# DFPlayer-Wemos-ESPHome.net
KiCad netlist of a schematic drawn in EAGLE
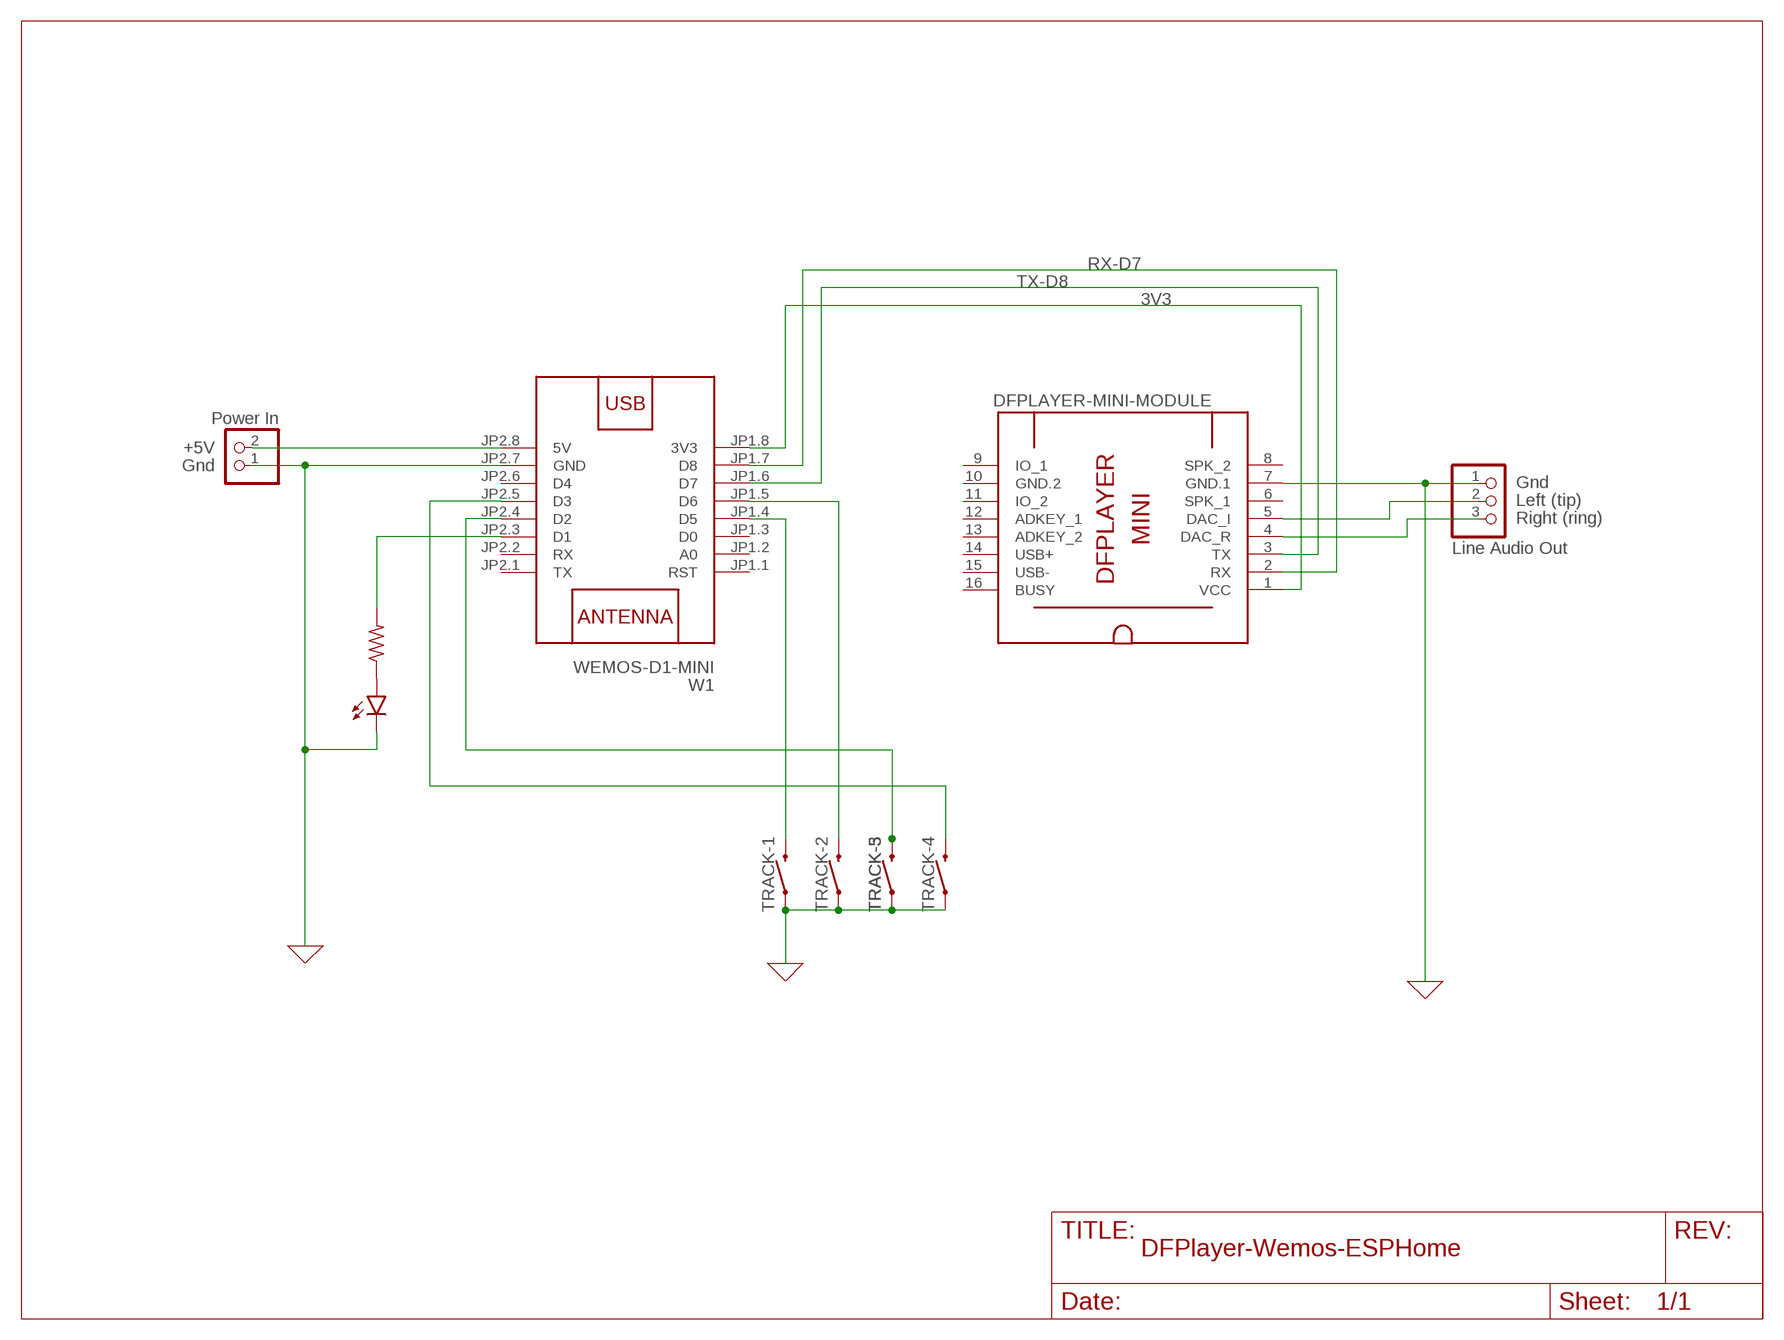
[diagram p0: schematic, sheet 1]

(export (version "E")
  (design (tool "Eeschema 10.0.6"))
  (components
    (comp (ref "D1")
      (value "WP7113SGD")
      (footprint "eagle-import:RADIAL_5MM")
      (fields
        (field (name "DIGIKEY_PART_NUMBER") "754-1735-ND")
        (field (name "MANUFACTURER") "Kingbright")
        (field (name "CREATED_BY") "PCBLayout.com")
      )
      (libsource (lib "eagle-import") (part "WP7113SGD"))
    )
    (comp (ref "JP2")
      (value "Line Audio Out")
      (footprint "eagle-import:1X03")
      (libsource (lib "eagle-import") (part "PINHD-1X3"))
    )
    (comp (ref "JP3")
      (value "Power In")
      (footprint "eagle-import:1X02")
      (libsource (lib "eagle-import") (part "PINHD-1X2"))
    )
    (comp (ref "R1")
      (value "R-US_0204/5")
      (footprint "eagle-import:0204_5")
      (libsource (lib "eagle-import") (part "R-US_0204/5"))
    )
    (comp (ref "TRACK-1")
      (value "MOMENTARY-SWITCH-SPST-PTH-6.0MM")
      (footprint "eagle-import:TACTILE_SWITCH_PTH_6.0MM")
      (libsource (lib "eagle-import") (part "MOMENTARY-SWITCH-SPST-PTH-6.0MM"))
    )
    (comp (ref "TRACK-2")
      (value "MOMENTARY-SWITCH-SPST-PTH-6.0MM")
      (footprint "eagle-import:TACTILE_SWITCH_PTH_6.0MM")
      (libsource (lib "eagle-import") (part "MOMENTARY-SWITCH-SPST-PTH-6.0MM"))
    )
    (comp (ref "TRACK-3")
      (value "MOMENTARY-SWITCH-SPST-PTH-6.0MM")
      (footprint "eagle-import:TACTILE_SWITCH_PTH_6.0MM")
      (libsource (lib "eagle-import") (part "MOMENTARY-SWITCH-SPST-PTH-6.0MM"))
    )
    (comp (ref "TRACK-4")
      (value "MOMENTARY-SWITCH-SPST-PTH-6.0MM")
      (footprint "eagle-import:TACTILE_SWITCH_PTH_6.0MM")
      (libsource (lib "eagle-import") (part "MOMENTARY-SWITCH-SPST-PTH-6.0MM"))
    )
    (comp (ref "TRACK-5")
      (value "MOMENTARY-SWITCH-SPST-PTH-6.0MM")
      (footprint "eagle-import:TACTILE_SWITCH_PTH_6.0MM")
      (libsource (lib "eagle-import") (part "MOMENTARY-SWITCH-SPST-PTH-6.0MM"))
    )
    (comp (ref "U$1")
      (value "DFPLAYER-MINI-MODULE")
      (footprint "eagle-import:DFPLAYER-MINI-MODULE")
      (libsource (lib "eagle-import") (part "DFPLAYER-MINI-MODULE"))
    )
    (comp (ref "W1")
      (value "WEMOS-D1-MINI")
      (footprint "eagle-import:WEMOS-D1-MINI")
      (libsource (lib "eagle-import") (part "WEMOS-D1-MINI"))
    )
  )
  (nets
    (net (code "1") (name "/3V3") (class "Default")
      (node (ref "U$1") (pin "1") (pinfunction "VCC_1") (pintype "power_in"))
      (node (ref "W1") (pin "JP1.8") (pinfunction "3V3_JP1.8") (pintype "power_in"))
    )
    (net (code "2") (name "/GND.2") (class "Default")
      (node (ref "U$1") (pin "10") (pinfunction "GND.2_10") (pintype "power_in"))
    )
    (net (code "3") (name "/RX-D7") (class "Default")
      (node (ref "U$1") (pin "2") (pinfunction "RX_2") (pintype "bidirectional"))
      (node (ref "W1") (pin "JP1.7") (pinfunction "D8_JP1.7") (pintype "bidirectional"))
    )
    (net (code "4") (name "/TX-D8") (class "Default")
      (node (ref "U$1") (pin "3") (pinfunction "TX_3") (pintype "bidirectional"))
      (node (ref "W1") (pin "JP1.6") (pinfunction "D7_JP1.6") (pintype "bidirectional"))
    )
    (net (code "5") (name "GND") (class "Default")
      (node (ref "D1") (pin "C") (pinfunction "C_C") (pintype "passive"))
      (node (ref "JP2") (pin "1") (pinfunction "1_1") (pintype "passive"))
      (node (ref "JP3") (pin "1") (pinfunction "1_1") (pintype "passive"))
      (node (ref "TRACK-1") (pin "1") (pinfunction "1_1") (pintype "passive"))
      (node (ref "TRACK-2") (pin "1") (pinfunction "1_1") (pintype "passive"))
      (node (ref "TRACK-3") (pin "1") (pinfunction "1_1") (pintype "passive"))
      (node (ref "TRACK-4") (pin "1") (pinfunction "1_1") (pintype "passive"))
      (node (ref "TRACK-5") (pin "1") (pinfunction "1_1") (pintype "passive"))
      (node (ref "U$1") (pin "7") (pinfunction "GND.1_7") (pintype "power_in"))
      (node (ref "W1") (pin "JP2.7") (pinfunction "GND_JP2.7") (pintype "power_in"))
    )
    (net (code "6") (name "Net-(D1-PadA)") (class "Default")
      (node (ref "D1") (pin "A") (pinfunction "A_A") (pintype "passive"))
      (node (ref "R1") (pin "1") (pinfunction "1_1") (pintype "passive"))
    )
    (net (code "7") (name "Net-(TRACK-1-2)") (class "Default")
      (node (ref "TRACK-1") (pin "3") (pinfunction "2_3") (pintype "passive"))
      (node (ref "W1") (pin "JP1.4") (pinfunction "D5_JP1.4") (pintype "bidirectional"))
    )
    (net (code "8") (name "Net-(TRACK-2-2)") (class "Default")
      (node (ref "TRACK-2") (pin "3") (pinfunction "2_3") (pintype "passive"))
      (node (ref "W1") (pin "JP1.5") (pinfunction "D6_JP1.5") (pintype "bidirectional"))
    )
    (net (code "9") (name "Net-(TRACK-3-2)") (class "Default")
      (node (ref "TRACK-3") (pin "3") (pinfunction "2_3") (pintype "passive"))
      (node (ref "TRACK-5") (pin "3") (pinfunction "2_3") (pintype "passive"))
      (node (ref "W1") (pin "JP2.4") (pinfunction "D2_JP2.4") (pintype "bidirectional"))
    )
    (net (code "10") (name "Net-(TRACK-4-2)") (class "Default")
      (node (ref "TRACK-4") (pin "3") (pinfunction "2_3") (pintype "passive"))
      (node (ref "W1") (pin "JP2.5") (pinfunction "D3_JP2.5") (pintype "bidirectional"))
    )
    (net (code "11") (name "Net-(U$1-DAC_I)") (class "Default")
      (node (ref "JP2") (pin "2") (pinfunction "2_2") (pintype "passive"))
      (node (ref "U$1") (pin "5") (pinfunction "DAC_I_5") (pintype "bidirectional"))
    )
    (net (code "12") (name "Net-(U$1-DAC_R)") (class "Default")
      (node (ref "JP2") (pin "3") (pinfunction "3_3") (pintype "passive"))
      (node (ref "U$1") (pin "4") (pinfunction "DAC_R_4") (pintype "bidirectional"))
    )
    (net (code "13") (name "Net-(W1-5V)") (class "Default")
      (node (ref "JP3") (pin "2") (pinfunction "2_2") (pintype "passive"))
      (node (ref "W1") (pin "JP2.8") (pinfunction "5V_JP2.8") (pintype "power_in"))
    )
    (net (code "14") (name "Net-(W1-D1)") (class "Default")
      (node (ref "R1") (pin "2") (pinfunction "2_2") (pintype "passive"))
      (node (ref "W1") (pin "JP2.3") (pinfunction "D1_JP2.3") (pintype "bidirectional"))
    )
    (net (code "15") (name "unconnected-(U$1-ADKEY_1-Pad12)") (class "Default")
      (node (ref "U$1") (pin "12") (pinfunction "ADKEY_1_12") (pintype "bidirectional"))
    )
    (net (code "16") (name "unconnected-(U$1-ADKEY_2-Pad13)") (class "Default")
      (node (ref "U$1") (pin "13") (pinfunction "ADKEY_2_13") (pintype "bidirectional"))
    )
    (net (code "17") (name "unconnected-(U$1-BUSY-Pad16)") (class "Default")
      (node (ref "U$1") (pin "16") (pinfunction "BUSY_16") (pintype "bidirectional"))
    )
    (net (code "18") (name "unconnected-(U$1-IO_1-Pad9)") (class "Default")
      (node (ref "U$1") (pin "9") (pinfunction "IO_1_9") (pintype "bidirectional"))
    )
    (net (code "19") (name "unconnected-(U$1-IO_2-Pad11)") (class "Default")
      (node (ref "U$1") (pin "11") (pinfunction "IO_2_11") (pintype "bidirectional"))
    )
    (net (code "20") (name "unconnected-(U$1-SPK_1-Pad6)") (class "Default")
      (node (ref "U$1") (pin "6") (pinfunction "SPK_1_6") (pintype "bidirectional"))
    )
    (net (code "21") (name "unconnected-(U$1-SPK_2-Pad8)") (class "Default")
      (node (ref "U$1") (pin "8") (pinfunction "SPK_2_8") (pintype "bidirectional"))
    )
    (net (code "22") (name "unconnected-(U$1-USB+-Pad14)") (class "Default")
      (node (ref "U$1") (pin "14") (pinfunction "USB+_14") (pintype "bidirectional"))
    )
    (net (code "23") (name "unconnected-(U$1-USB--Pad15)") (class "Default")
      (node (ref "U$1") (pin "15") (pinfunction "USB-_15") (pintype "bidirectional"))
    )
    (net (code "24") (name "unconnected-(W1-A0-PadJP1.2)") (class "Default")
      (node (ref "W1") (pin "JP1.2") (pinfunction "A0_JP1.2") (pintype "bidirectional"))
    )
    (net (code "25") (name "unconnected-(W1-D0-PadJP1.3)") (class "Default")
      (node (ref "W1") (pin "JP1.3") (pinfunction "D0_JP1.3") (pintype "bidirectional"))
    )
    (net (code "26") (name "unconnected-(W1-D4-PadJP2.6)") (class "Default")
      (node (ref "W1") (pin "JP2.6") (pinfunction "D4_JP2.6") (pintype "bidirectional"))
    )
    (net (code "27") (name "unconnected-(W1-RST-PadJP1.1)") (class "Default")
      (node (ref "W1") (pin "JP1.1") (pinfunction "RST_JP1.1") (pintype "bidirectional"))
    )
    (net (code "28") (name "unconnected-(W1-RX-PadJP2.2)") (class "Default")
      (node (ref "W1") (pin "JP2.2") (pinfunction "RX_JP2.2") (pintype "bidirectional"))
    )
    (net (code "29") (name "unconnected-(W1-TX-PadJP2.1)") (class "Default")
      (node (ref "W1") (pin "JP2.1") (pinfunction "TX_JP2.1") (pintype "bidirectional"))
    )
  )
)
